# LaserControl.net
KiCad netlist of a schematic drawn in Altium Designer
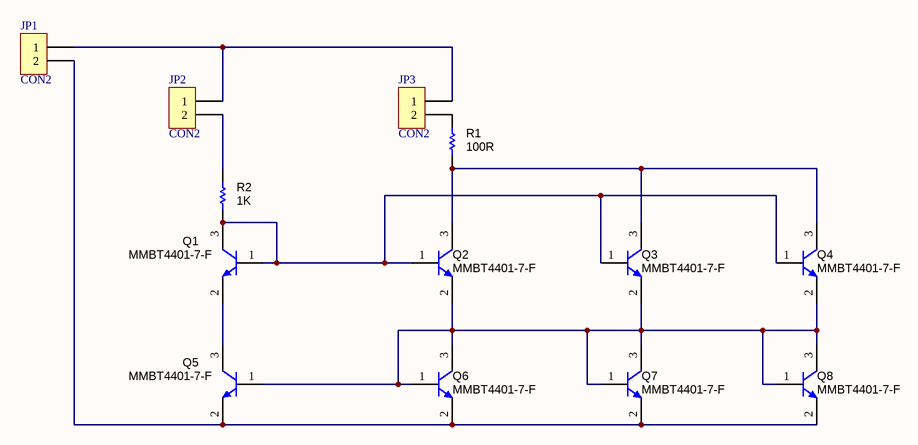
[diagram p0: LaserControl.SchDoc]

(export (version "E")
  (design (tool "Eeschema 10.0.6"))
  (components
    (comp (ref "JP1")
      (value "CON2")
      (footprint "SIP2")
      (description "Connector")
      (libsource (lib "Steve") (part "CON2"))
    )
    (comp (ref "JP2")
      (value "CON2")
      (footprint "SIP2")
      (description "Connector")
      (libsource (lib "Steve") (part "CON2"))
    )
    (comp (ref "JP3")
      (value "CON2")
      (footprint "SIP2")
      (description "Connector")
      (libsource (lib "Steve") (part "CON2"))
    )
    (comp (ref "Q1")
      (value "MMBT4401-7-F")
      (footprint "SOT-23")
      (description "Transistor, NPN, 40 V, 0.15 A, SOT-23")
      (fields (field (name "MANUFACTURER") "Diodes Inc.") (field (name "PUBLISHER") "Texas Instruments"))
      (libsource (lib "Bipolar_Transistor") (part "MMBT4401-7-F, Diodes Inc."))
    )
    (comp (ref "Q2")
      (value "MMBT4401-7-F")
      (footprint "SOT-23")
      (description "Transistor, NPN, 40 V, 0.15 A, SOT-23")
      (fields (field (name "MANUFACTURER") "Diodes Inc.") (field (name "PUBLISHER") "Texas Instruments"))
      (libsource (lib "Bipolar_Transistor") (part "MMBT4401-7-F, Diodes Inc."))
    )
    (comp (ref "Q3")
      (value "MMBT4401-7-F")
      (footprint "SOT-23")
      (description "Transistor, NPN, 40 V, 0.15 A, SOT-23")
      (fields (field (name "MANUFACTURER") "Diodes Inc.") (field (name "PUBLISHER") "Texas Instruments"))
      (libsource (lib "Bipolar_Transistor") (part "MMBT4401-7-F, Diodes Inc."))
    )
    (comp (ref "Q4")
      (value "MMBT4401-7-F")
      (footprint "SOT-23")
      (description "Transistor, NPN, 40 V, 0.15 A, SOT-23")
      (fields (field (name "MANUFACTURER") "Diodes Inc.") (field (name "PUBLISHER") "Texas Instruments"))
      (libsource (lib "Bipolar_Transistor") (part "MMBT4401-7-F, Diodes Inc."))
    )
    (comp (ref "Q5")
      (value "MMBT4401-7-F")
      (footprint "SOT-23")
      (description "Transistor, NPN, 40 V, 0.15 A, SOT-23")
      (fields (field (name "MANUFACTURER") "Diodes Inc.") (field (name "PUBLISHER") "Texas Instruments"))
      (libsource (lib "Bipolar_Transistor") (part "MMBT4401-7-F, Diodes Inc."))
    )
    (comp (ref "Q6")
      (value "MMBT4401-7-F")
      (footprint "SOT-23")
      (description "Transistor, NPN, 40 V, 0.15 A, SOT-23")
      (fields (field (name "MANUFACTURER") "Diodes Inc.") (field (name "PUBLISHER") "Texas Instruments"))
      (libsource (lib "Bipolar_Transistor") (part "MMBT4401-7-F, Diodes Inc."))
    )
    (comp (ref "Q7")
      (value "MMBT4401-7-F")
      (footprint "SOT-23")
      (description "Transistor, NPN, 40 V, 0.15 A, SOT-23")
      (fields (field (name "MANUFACTURER") "Diodes Inc.") (field (name "PUBLISHER") "Texas Instruments"))
      (libsource (lib "Bipolar_Transistor") (part "MMBT4401-7-F, Diodes Inc."))
    )
    (comp (ref "Q8")
      (value "MMBT4401-7-F")
      (footprint "SOT-23")
      (description "Transistor, NPN, 40 V, 0.15 A, SOT-23")
      (fields (field (name "MANUFACTURER") "Diodes Inc.") (field (name "PUBLISHER") "Texas Instruments"))
      (libsource (lib "Bipolar_Transistor") (part "MMBT4401-7-F, Diodes Inc."))
    )
    (comp (ref "R1")
      (value "100R")
      (footprint "0603")
      (fields
        (field (name "PARTNUMBER") "RC0603FR-07180RL")
        (field (name "MANUFACTURER") "Yageo America")
        (field (name "PUBLISHER") "Texas Instruments")
      )
      (libsource (lib "Resistor_0603") (part "RC0603FR-07180RL"))
    )
    (comp (ref "R2")
      (value "1K")
      (footprint "0603")
      (fields
        (field (name "PARTNUMBER") "RC0603FR-07180RL")
        (field (name "MANUFACTURER") "Yageo America")
        (field (name "PUBLISHER") "Texas Instruments")
      )
      (libsource (lib "Resistor_0603") (part "RC0603FR-07180RL"))
    )
  )
  (nets
    (net (code "1") (name "Net-(JP1-Pad1)") (class "Default")
      (node (ref "JP1") (pin "1") (pinfunction "1_1") (pintype "passive"))
      (node (ref "JP2") (pin "1") (pinfunction "1_1") (pintype "passive"))
      (node (ref "JP3") (pin "1") (pinfunction "1_1") (pintype "passive"))
    )
    (net (code "2") (name "Net-(JP2-Pad2)") (class "Default")
      (node (ref "JP2") (pin "2") (pinfunction "2_2") (pintype "passive"))
      (node (ref "R2") (pin "1") (pinfunction "1_1") (pintype "passive"))
    )
    (net (code "3") (name "Net-(JP3-Pad2)") (class "Default")
      (node (ref "JP3") (pin "2") (pinfunction "2_2") (pintype "passive"))
      (node (ref "R1") (pin "1") (pinfunction "1_1") (pintype "passive"))
    )
    (net (code "4") (name "Net-(Q1-B)") (class "Default")
      (node (ref "Q1") (pin "1") (pinfunction "B_1") (pintype "passive"))
      (node (ref "Q1") (pin "3") (pinfunction "C_3") (pintype "passive"))
      (node (ref "Q2") (pin "1") (pinfunction "B_1") (pintype "passive"))
      (node (ref "Q3") (pin "1") (pinfunction "B_1") (pintype "passive"))
      (node (ref "Q4") (pin "1") (pinfunction "B_1") (pintype "passive"))
      (node (ref "R2") (pin "2") (pinfunction "2_2") (pintype "passive"))
    )
    (net (code "5") (name "Net-(Q1-E)") (class "Default")
      (node (ref "Q1") (pin "2") (pinfunction "E_2") (pintype "passive"))
      (node (ref "Q5") (pin "3") (pinfunction "C_3") (pintype "passive"))
    )
    (net (code "6") (name "Net-(Q2-C)") (class "Default")
      (node (ref "Q2") (pin "3") (pinfunction "C_3") (pintype "passive"))
      (node (ref "Q3") (pin "3") (pinfunction "C_3") (pintype "passive"))
      (node (ref "Q4") (pin "3") (pinfunction "C_3") (pintype "passive"))
      (node (ref "R1") (pin "2") (pinfunction "2_2") (pintype "passive"))
    )
    (net (code "7") (name "Net-(Q2-E)") (class "Default")
      (node (ref "Q2") (pin "2") (pinfunction "E_2") (pintype "passive"))
      (node (ref "Q3") (pin "2") (pinfunction "E_2") (pintype "passive"))
      (node (ref "Q4") (pin "2") (pinfunction "E_2") (pintype "passive"))
      (node (ref "Q5") (pin "1") (pinfunction "B_1") (pintype "passive"))
      (node (ref "Q6") (pin "1") (pinfunction "B_1") (pintype "passive"))
      (node (ref "Q6") (pin "3") (pinfunction "C_3") (pintype "passive"))
      (node (ref "Q7") (pin "1") (pinfunction "B_1") (pintype "passive"))
      (node (ref "Q7") (pin "3") (pinfunction "C_3") (pintype "passive"))
      (node (ref "Q8") (pin "1") (pinfunction "B_1") (pintype "passive"))
      (node (ref "Q8") (pin "3") (pinfunction "C_3") (pintype "passive"))
    )
    (net (code "8") (name "Net-(Q5-E)") (class "Default")
      (node (ref "JP1") (pin "2") (pinfunction "2_2") (pintype "passive"))
      (node (ref "Q5") (pin "2") (pinfunction "E_2") (pintype "passive"))
      (node (ref "Q6") (pin "2") (pinfunction "E_2") (pintype "passive"))
      (node (ref "Q7") (pin "2") (pinfunction "E_2") (pintype "passive"))
      (node (ref "Q8") (pin "2") (pinfunction "E_2") (pintype "passive"))
    )
  )
)
